# rpi_adapter_mipi_in_out.net
KiCad netlist of a schematic drawn in Altium Designer
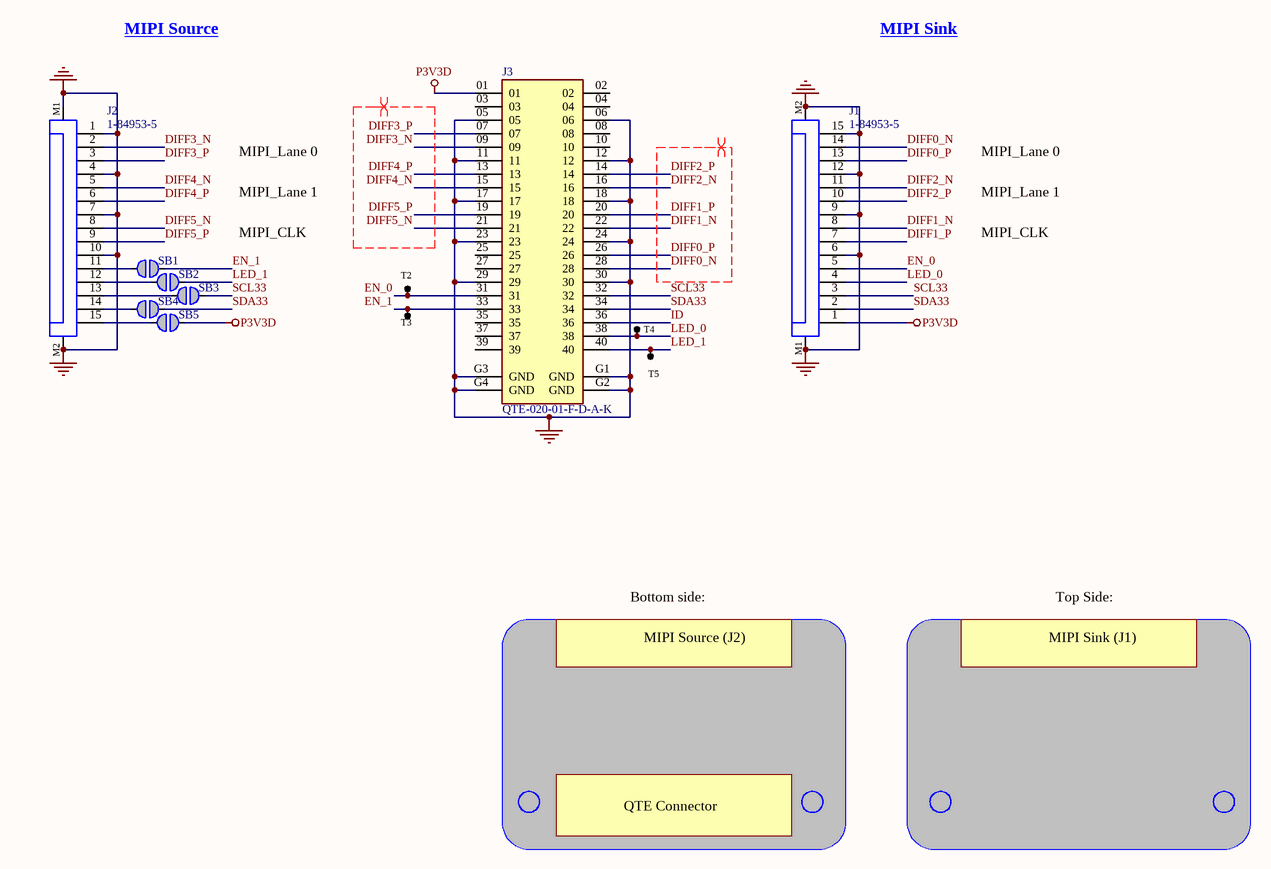
[diagram p0: rpi_adapter_mipi_in_out.SchDoc]

(export (version "E")
  (design (tool "Eeschema 10.0.6"))
  (components
    (comp (ref "J1")
      (value "1-84953-5")
      (footprint "TE_1-84953-5")
      (description "Conn FPC Connector SKT 15 POS 1mm Solder RA SMD T/R")
      (fields (field (name "MANUFACTURER") "TE Connectivity"))
      (libsource (lib "rpi_adapter") (part "FPC - 15P - 2MP"))
    )
    (comp (ref "J2")
      (value "1-84953-5")
      (footprint "TE_1-84953-5")
      (description "Conn FPC Connector SKT 15 POS 1mm Solder RA SMD T/R")
      (fields (field (name "MANUFACTURER") "TE Connectivity"))
      (libsource (lib "rpi_adapter") (part "FPC - 15P - 2MP"))
    )
    (comp (ref "J3")
      (value "QTE-020-01-F-D-A-K")
      (footprint "SAMTEC_QTE-020-01-X-D-A")
      (description "Q Strip® High-Speed Ground Plane Header, 0.80mm Pitch")
      (fields
        (field (name "MANUFACTURER") "Samtec")
        (field (name "MANUFACTURER PART NUMBER") "QTE-020-01-F-D-A")
      )
      (libsource (lib "NX Module baseboard") (part "QSE-020-01-F-D-A-K"))
    )
    (comp (ref "SB1")
      (value "Solderbridge")
      (footprint "Solderbridge")
      (fields (field (name "PUBLISHER") "Nordic Semiconductor"))
      (libsource (lib "AiC") (part "Solderbridge"))
    )
    (comp (ref "SB2")
      (value "Solderbridge")
      (footprint "Solderbridge")
      (fields (field (name "PUBLISHER") "Nordic Semiconductor"))
      (libsource (lib "AiC") (part "Solderbridge"))
    )
    (comp (ref "SB3")
      (value "Solderbridge")
      (footprint "Solderbridge")
      (fields (field (name "PUBLISHER") "Nordic Semiconductor"))
      (libsource (lib "AiC") (part "Solderbridge"))
    )
    (comp (ref "SB4")
      (value "Solderbridge")
      (footprint "Solderbridge")
      (fields (field (name "PUBLISHER") "Nordic Semiconductor"))
      (libsource (lib "AiC") (part "Solderbridge"))
    )
    (comp (ref "SB5")
      (value "Solderbridge")
      (footprint "Solderbridge")
      (fields (field (name "PUBLISHER") "Nordic Semiconductor"))
      (libsource (lib "AiC") (part "Solderbridge"))
    )
    (comp (ref "T2")
      (value "TP_S")
      (footprint "TP 1mm")
      (description "test point")
      (libsource (lib "AiC") (part "TP_S"))
    )
    (comp (ref "T3")
      (value "TP_S")
      (footprint "TP 1mm")
      (description "test point")
      (libsource (lib "AiC") (part "TP_S"))
    )
    (comp (ref "T4")
      (value "TP_S")
      (footprint "TP 1mm")
      (description "test point")
      (libsource (lib "AiC") (part "TP_S"))
    )
    (comp (ref "T5")
      (value "TP_S")
      (footprint "TP 1mm")
      (description "test point")
      (libsource (lib "AiC") (part "TP_S"))
    )
  )
  (nets
    (net (code "1") (name "/DIFF0_N") (class "Default")
      (node (ref "J1") (pin "14") (pinfunction "14_14") (pintype "passive"))
      (node (ref "J3") (pin "28") (pinfunction "28_28") (pintype "passive"))
    )
    (net (code "2") (name "/DIFF0_P") (class "Default")
      (node (ref "J1") (pin "13") (pinfunction "13_13") (pintype "passive"))
      (node (ref "J3") (pin "26") (pinfunction "26_26") (pintype "passive"))
    )
    (net (code "3") (name "/DIFF1_N") (class "Default")
      (node (ref "J1") (pin "8") (pinfunction "8_8") (pintype "passive"))
      (node (ref "J3") (pin "22") (pinfunction "22_22") (pintype "passive"))
    )
    (net (code "4") (name "/DIFF1_P") (class "Default")
      (node (ref "J1") (pin "7") (pinfunction "7_7") (pintype "passive"))
      (node (ref "J3") (pin "20") (pinfunction "20_20") (pintype "passive"))
    )
    (net (code "5") (name "/DIFF2_N") (class "Default")
      (node (ref "J1") (pin "11") (pinfunction "11_11") (pintype "passive"))
      (node (ref "J3") (pin "16") (pinfunction "16_16") (pintype "passive"))
    )
    (net (code "6") (name "/DIFF2_P") (class "Default")
      (node (ref "J1") (pin "10") (pinfunction "10_10") (pintype "passive"))
      (node (ref "J3") (pin "14") (pinfunction "14_14") (pintype "passive"))
    )
    (net (code "7") (name "/DIFF3_N") (class "Default")
      (node (ref "J2") (pin "2") (pinfunction "2_2") (pintype "passive"))
      (node (ref "J3") (pin "09") (pinfunction "09_09") (pintype "passive"))
    )
    (net (code "8") (name "/DIFF3_P") (class "Default")
      (node (ref "J2") (pin "3") (pinfunction "3_3") (pintype "passive"))
      (node (ref "J3") (pin "07") (pinfunction "07_07") (pintype "passive"))
    )
    (net (code "9") (name "/DIFF4_N") (class "Default")
      (node (ref "J2") (pin "5") (pinfunction "5_5") (pintype "passive"))
      (node (ref "J3") (pin "15") (pinfunction "15_15") (pintype "passive"))
    )
    (net (code "10") (name "/DIFF4_P") (class "Default")
      (node (ref "J2") (pin "6") (pinfunction "6_6") (pintype "passive"))
      (node (ref "J3") (pin "13") (pinfunction "13_13") (pintype "passive"))
    )
    (net (code "11") (name "/DIFF5_N") (class "Default")
      (node (ref "J2") (pin "8") (pinfunction "8_8") (pintype "passive"))
      (node (ref "J3") (pin "21") (pinfunction "21_21") (pintype "passive"))
    )
    (net (code "12") (name "/DIFF5_P") (class "Default")
      (node (ref "J2") (pin "9") (pinfunction "9_9") (pintype "passive"))
      (node (ref "J3") (pin "19") (pinfunction "19_19") (pintype "passive"))
    )
    (net (code "13") (name "/EN_0") (class "Default")
      (node (ref "J1") (pin "5") (pinfunction "5_5") (pintype "passive"))
      (node (ref "J3") (pin "31") (pinfunction "31_31") (pintype "passive"))
      (node (ref "T2") (pin "1") (pintype "passive"))
    )
    (net (code "14") (name "/EN_1") (class "Default")
      (node (ref "J3") (pin "33") (pinfunction "33_33") (pintype "passive"))
      (node (ref "SB1") (pin "1") (pinfunction "0_1") (pintype "passive"))
      (node (ref "T3") (pin "1") (pintype "passive"))
    )
    (net (code "15") (name "/ID") (class "Default")
      (node (ref "J3") (pin "36") (pinfunction "36_36") (pintype "passive"))
    )
    (net (code "16") (name "/LED_0") (class "Default")
      (node (ref "J1") (pin "4") (pinfunction "4_4") (pintype "passive"))
      (node (ref "J3") (pin "38") (pinfunction "38_38") (pintype "passive"))
      (node (ref "T4") (pin "1") (pintype "passive"))
    )
    (net (code "17") (name "/LED_1") (class "Default")
      (node (ref "J3") (pin "40") (pinfunction "40_40") (pintype "passive"))
      (node (ref "SB2") (pin "1") (pinfunction "0_1") (pintype "passive"))
      (node (ref "T5") (pin "1") (pintype "passive"))
    )
    (net (code "18") (name "/SCL33") (class "Default")
      (node (ref "J1") (pin "3") (pinfunction "3_3") (pintype "passive"))
      (node (ref "J3") (pin "32") (pinfunction "32_32") (pintype "passive"))
      (node (ref "SB3") (pin "1") (pinfunction "0_1") (pintype "passive"))
    )
    (net (code "19") (name "/SDA33") (class "Default")
      (node (ref "J1") (pin "2") (pinfunction "2_2") (pintype "passive"))
      (node (ref "J3") (pin "34") (pinfunction "34_34") (pintype "passive"))
      (node (ref "SB4") (pin "1") (pinfunction "0_1") (pintype "passive"))
    )
    (net (code "20") (name "GND") (class "Default")
      (node (ref "J1") (pin "12") (pinfunction "12_12") (pintype "passive"))
      (node (ref "J1") (pin "15") (pinfunction "15_15") (pintype "passive"))
      (node (ref "J1") (pin "6") (pinfunction "6_6") (pintype "passive"))
      (node (ref "J1") (pin "9") (pinfunction "9_9") (pintype "passive"))
      (node (ref "J1") (pin "M1") (pinfunction "M1_M1") (pintype "passive"))
      (node (ref "J1") (pin "M2") (pinfunction "M2_M2") (pintype "passive"))
      (node (ref "J2") (pin "1") (pinfunction "1_1") (pintype "passive"))
      (node (ref "J2") (pin "10") (pinfunction "10_10") (pintype "passive"))
      (node (ref "J2") (pin "4") (pinfunction "4_4") (pintype "passive"))
      (node (ref "J2") (pin "7") (pinfunction "7_7") (pintype "passive"))
      (node (ref "J2") (pin "M1") (pinfunction "M1_M1") (pintype "passive"))
      (node (ref "J2") (pin "M2") (pinfunction "M2_M2") (pintype "passive"))
      (node (ref "J3") (pin "05") (pinfunction "05_05") (pintype "passive"))
      (node (ref "J3") (pin "06") (pinfunction "06_06") (pintype "passive"))
      (node (ref "J3") (pin "11") (pinfunction "11_11") (pintype "passive"))
      (node (ref "J3") (pin "12") (pinfunction "12_12") (pintype "passive"))
      (node (ref "J3") (pin "17") (pinfunction "17_17") (pintype "passive"))
      (node (ref "J3") (pin "18") (pinfunction "18_18") (pintype "passive"))
      (node (ref "J3") (pin "23") (pinfunction "23_23") (pintype "passive"))
      (node (ref "J3") (pin "24") (pinfunction "24_24") (pintype "passive"))
      (node (ref "J3") (pin "29") (pinfunction "29_29") (pintype "passive"))
      (node (ref "J3") (pin "30") (pinfunction "30_30") (pintype "passive"))
      (node (ref "J3") (pin "G1") (pinfunction "GND_G1") (pintype "power_in"))
      (node (ref "J3") (pin "G2") (pinfunction "GND_G2") (pintype "power_in"))
      (node (ref "J3") (pin "G3") (pinfunction "GND_G3") (pintype "power_in"))
      (node (ref "J3") (pin "G4") (pinfunction "GND_G4") (pintype "power_in"))
    )
    (net (code "21") (name "Net-(SB1-1)") (class "Default")
      (node (ref "J2") (pin "11") (pinfunction "11_11") (pintype "passive"))
      (node (ref "SB1") (pin "2") (pinfunction "1_2") (pintype "passive"))
    )
    (net (code "22") (name "Net-(SB2-1)") (class "Default")
      (node (ref "J2") (pin "12") (pinfunction "12_12") (pintype "passive"))
      (node (ref "SB2") (pin "2") (pinfunction "1_2") (pintype "passive"))
    )
    (net (code "23") (name "Net-(SB3-1)") (class "Default")
      (node (ref "J2") (pin "13") (pinfunction "13_13") (pintype "passive"))
      (node (ref "SB3") (pin "2") (pinfunction "1_2") (pintype "passive"))
    )
    (net (code "24") (name "Net-(SB4-1)") (class "Default")
      (node (ref "J2") (pin "14") (pinfunction "14_14") (pintype "passive"))
      (node (ref "SB4") (pin "2") (pinfunction "1_2") (pintype "passive"))
    )
    (net (code "25") (name "Net-(SB5-1)") (class "Default")
      (node (ref "J2") (pin "15") (pinfunction "15_15") (pintype "passive"))
      (node (ref "SB5") (pin "2") (pinfunction "1_2") (pintype "passive"))
    )
    (net (code "26") (name "P3V3D") (class "Default")
      (node (ref "J1") (pin "1") (pinfunction "1_1") (pintype "passive"))
      (node (ref "J3") (pin "01") (pinfunction "01_01") (pintype "passive"))
      (node (ref "SB5") (pin "1") (pinfunction "0_1") (pintype "passive"))
    )
    (net (code "27") (name "unconnected-(J3-Pad02)") (class "Default")
      (node (ref "J3") (pin "02") (pinfunction "02_02") (pintype "passive"))
    )
    (net (code "28") (name "unconnected-(J3-Pad03)") (class "Default")
      (node (ref "J3") (pin "03") (pinfunction "03_03") (pintype "passive"))
    )
    (net (code "29") (name "unconnected-(J3-Pad04)") (class "Default")
      (node (ref "J3") (pin "04") (pinfunction "04_04") (pintype "passive"))
    )
    (net (code "30") (name "unconnected-(J3-Pad08)") (class "Default")
      (node (ref "J3") (pin "08") (pinfunction "08_08") (pintype "passive"))
    )
    (net (code "31") (name "unconnected-(J3-Pad10)") (class "Default")
      (node (ref "J3") (pin "10") (pinfunction "10_10") (pintype "passive"))
    )
    (net (code "32") (name "unconnected-(J3-Pad25)") (class "Default")
      (node (ref "J3") (pin "25") (pinfunction "25_25") (pintype "passive"))
    )
    (net (code "33") (name "unconnected-(J3-Pad27)") (class "Default")
      (node (ref "J3") (pin "27") (pinfunction "27_27") (pintype "passive"))
    )
    (net (code "34") (name "unconnected-(J3-Pad35)") (class "Default")
      (node (ref "J3") (pin "35") (pinfunction "35_35") (pintype "passive"))
    )
    (net (code "35") (name "unconnected-(J3-Pad37)") (class "Default")
      (node (ref "J3") (pin "37") (pinfunction "37_37") (pintype "passive"))
    )
    (net (code "36") (name "unconnected-(J3-Pad39)") (class "Default")
      (node (ref "J3") (pin "39") (pinfunction "39_39") (pintype "passive"))
    )
  )
)
